# sbb-shield.net
KiCad netlist of a schematic drawn in EAGLE
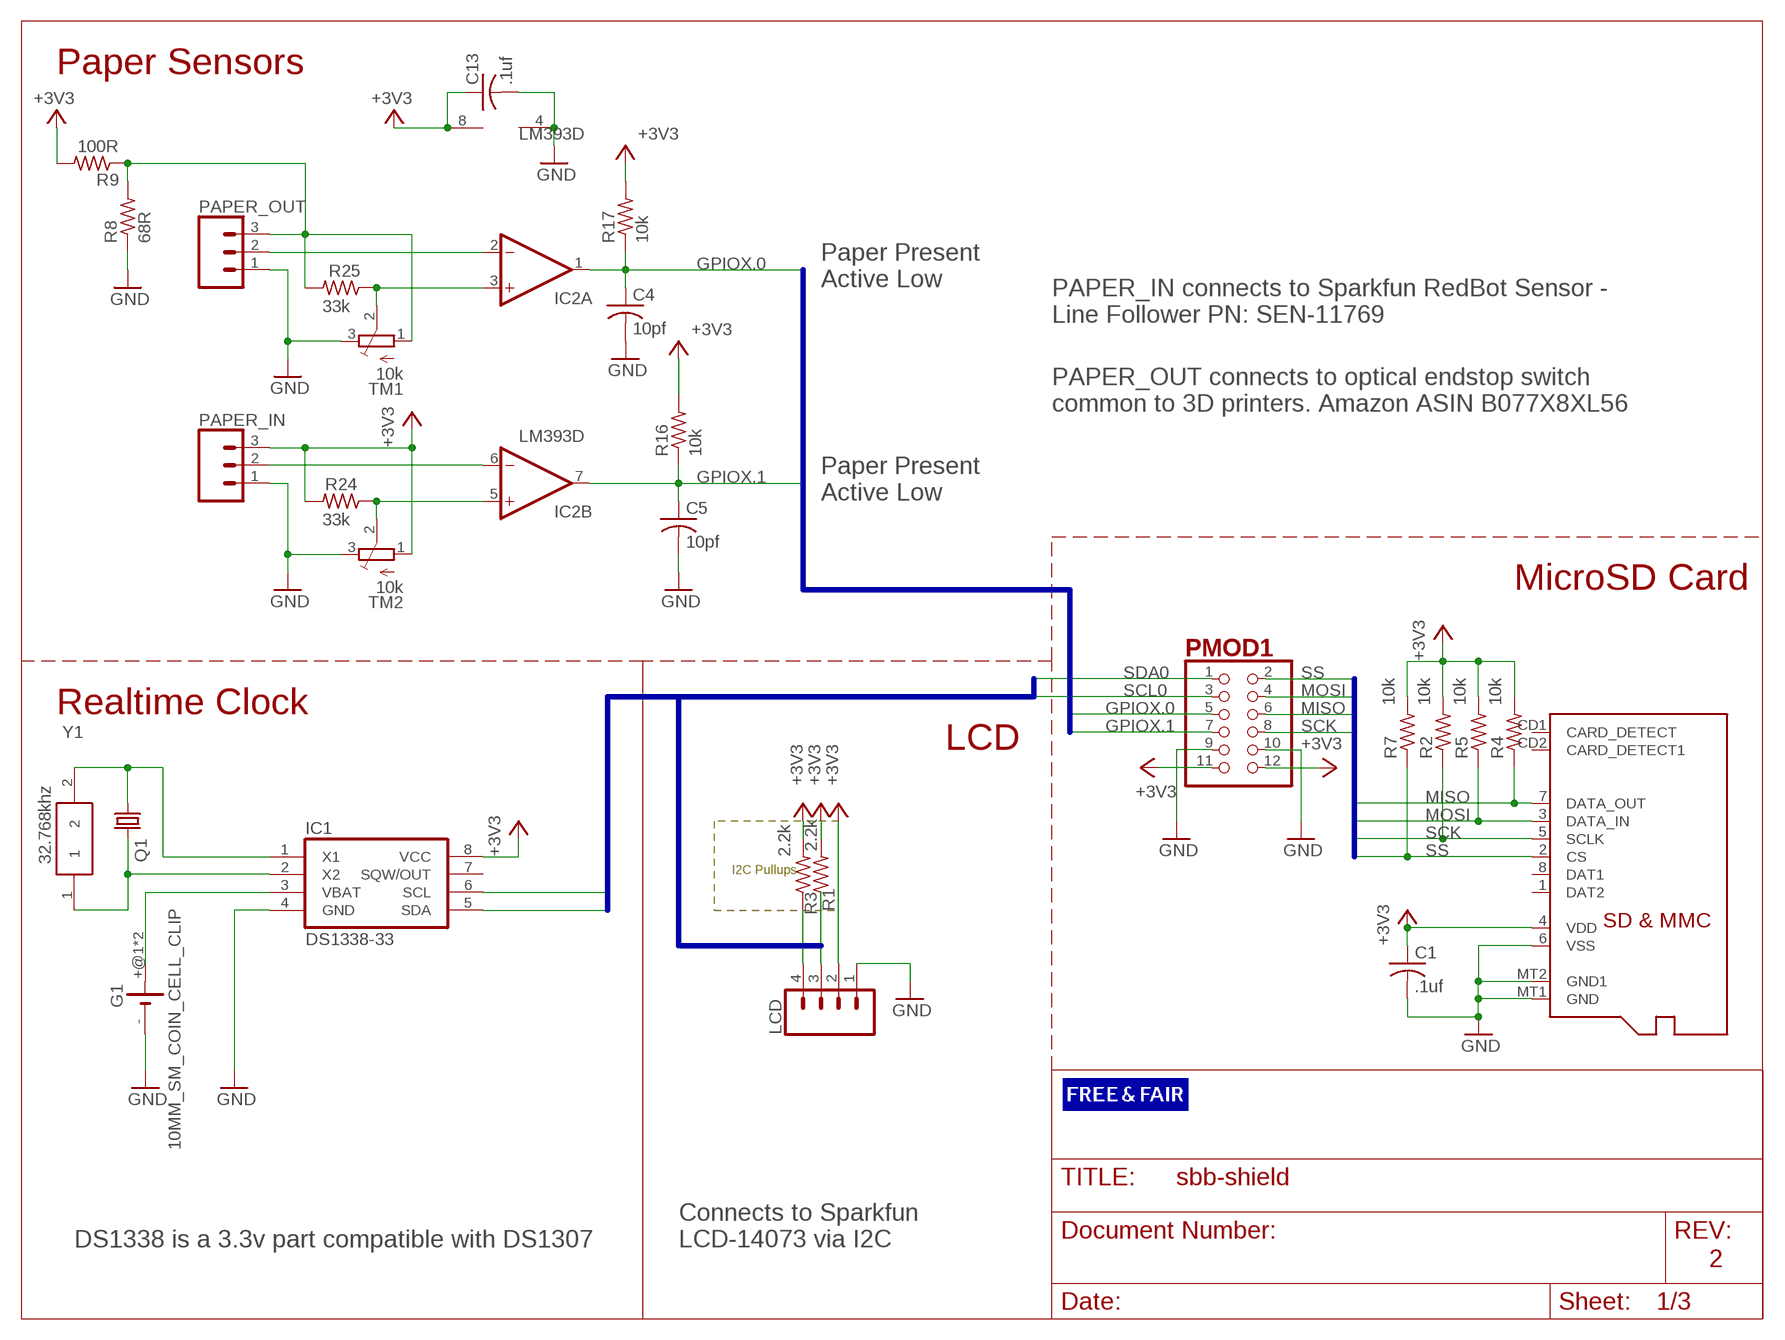
[diagram p0: schematic, sheet 1]
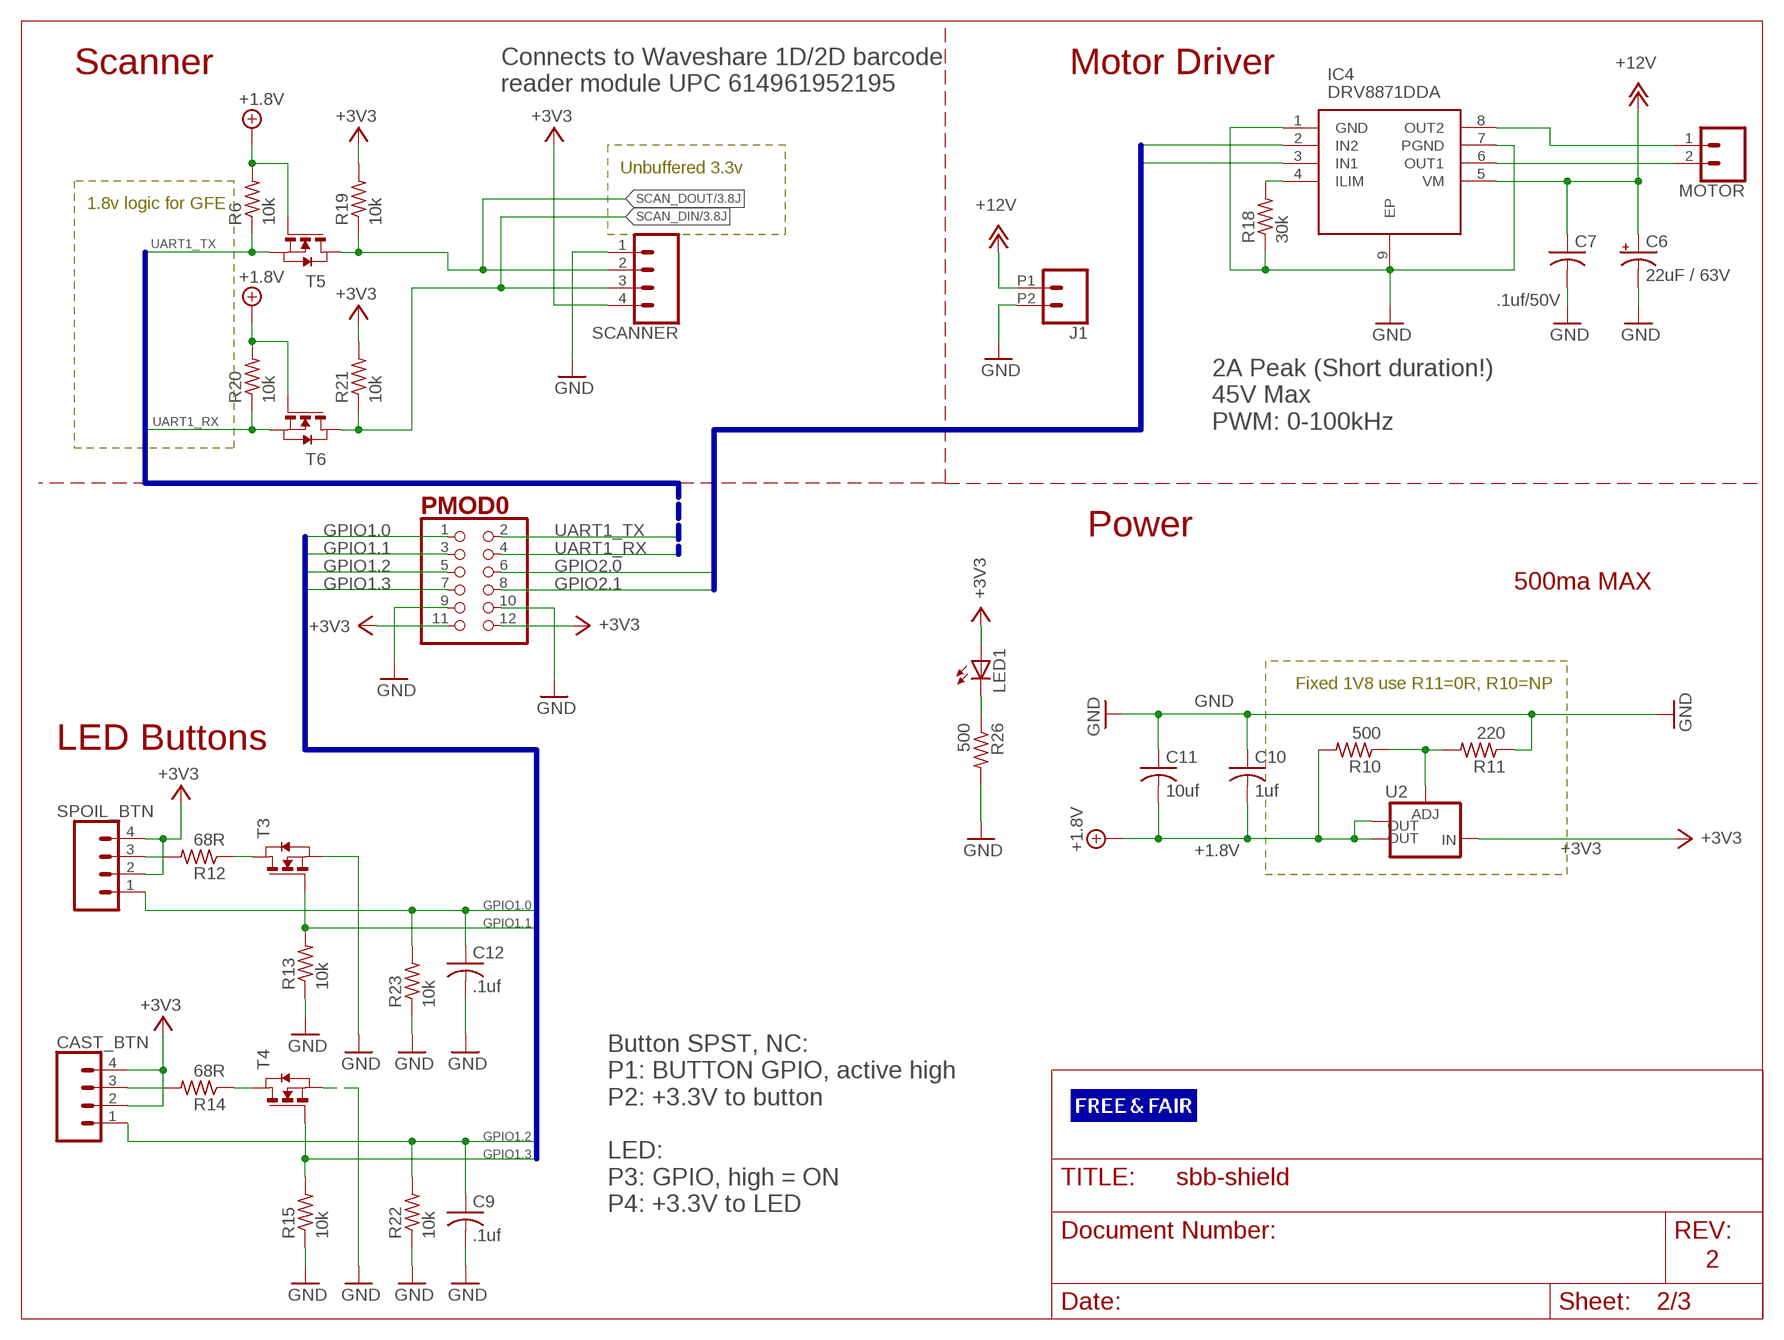
[diagram p1: schematic, sheet 2]
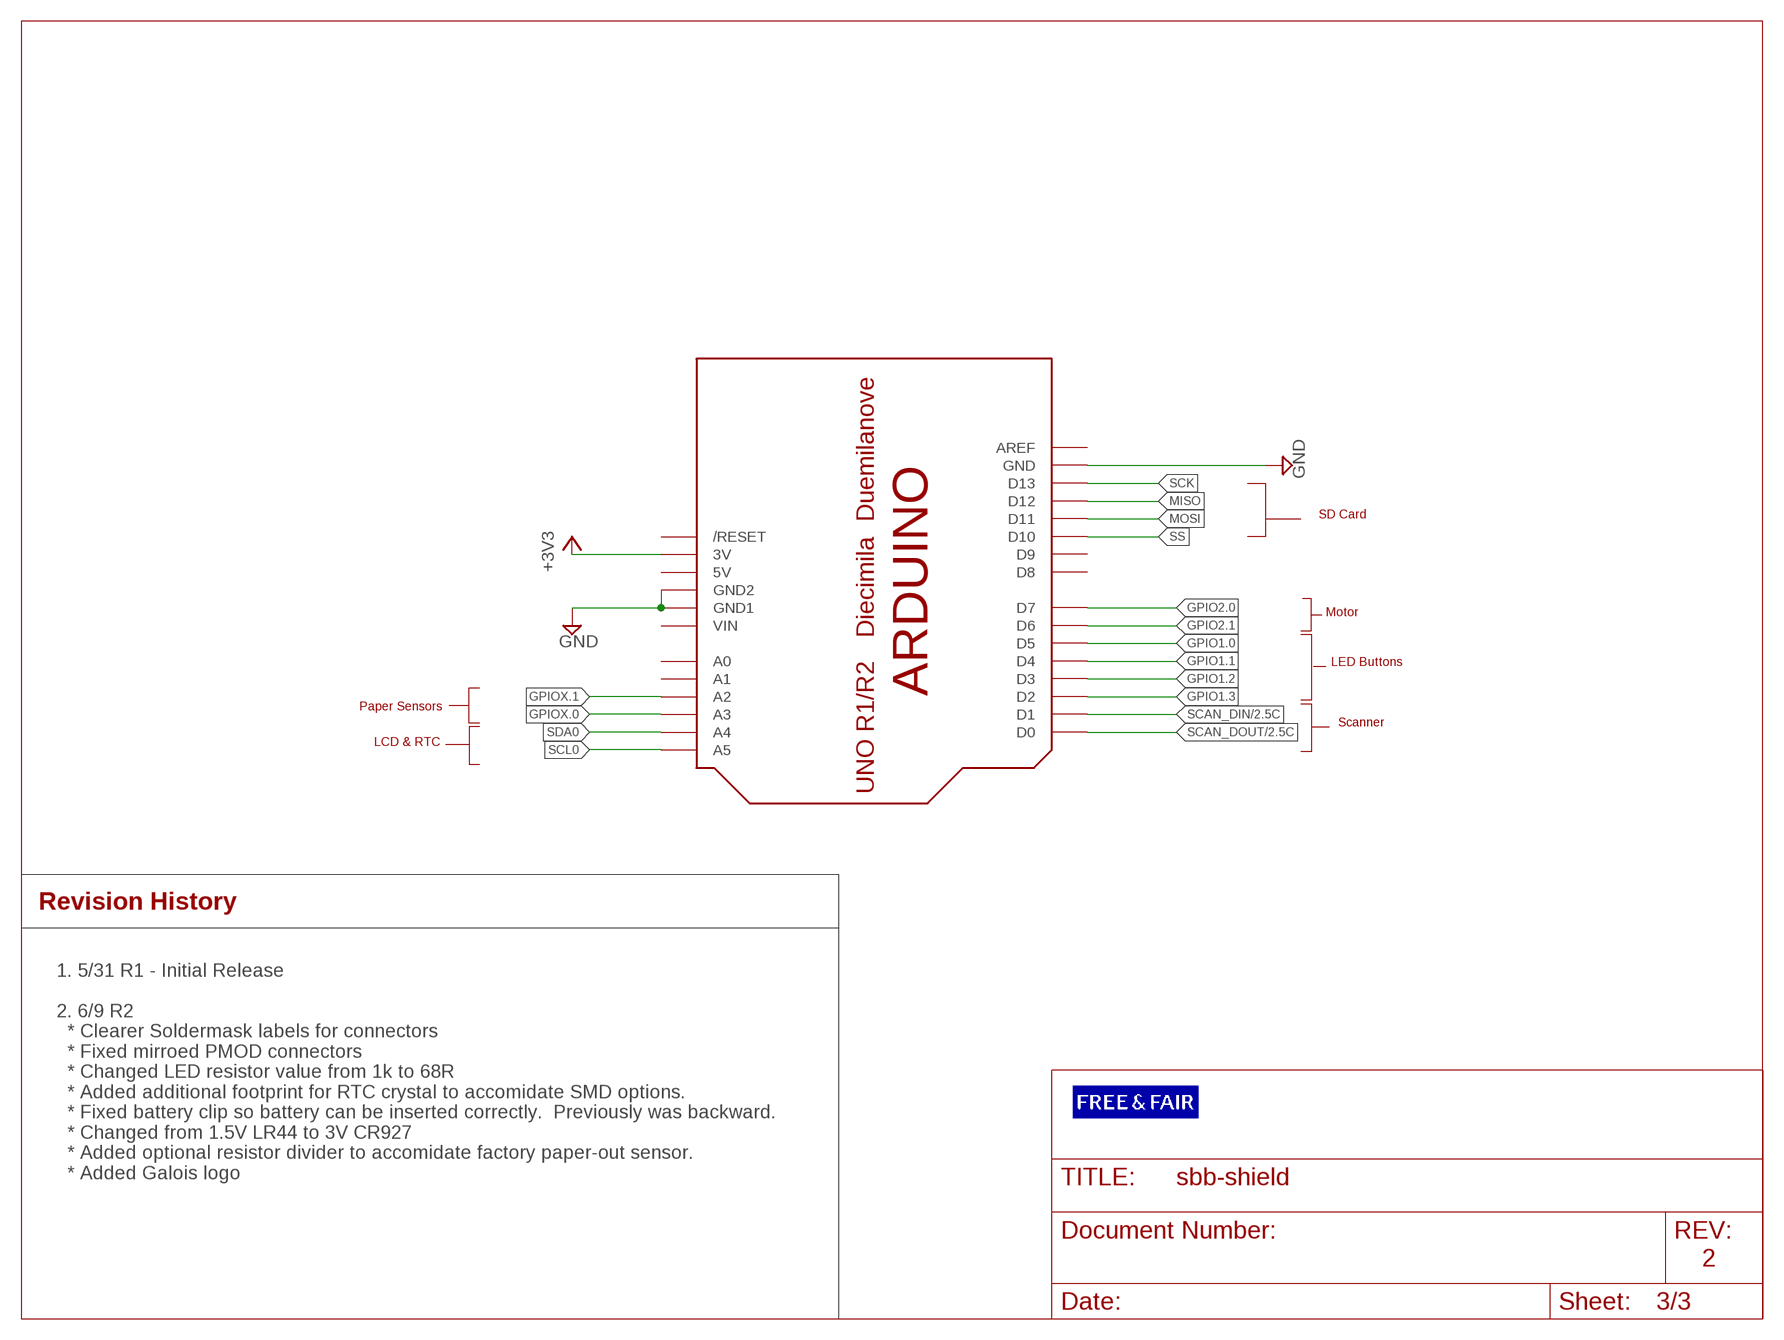
[diagram p2: schematic, sheet 3]

(export (version "E")
  (design (tool "Eeschema 10.0.6"))
  (components
    (comp (ref "U$2")
      (value "ARDUINO-NOHOLE")
      (footprint "eagle-import:ARDUINO-NOHOLE")
      (libsource (lib "eagle-import") (part "ARDUINO-NOHOLE"))
    )
    (comp (ref "C6")
      (value "22uF / 63V")
      (footprint "eagle-import:PANASONIC_D")
      (libsource (lib "eagle-import") (part "CPOL-USD"))
    )
    (comp (ref "C7")
      (value ".1uf/50V")
      (footprint "eagle-import:C0805K")
      (libsource (lib "eagle-import") (part "C-USC0805K"))
    )
    (comp (ref "C9")
      (value ".1uf")
      (footprint "eagle-import:C0603K")
      (libsource (lib "eagle-import") (part "rcl_334_C-USC0603K"))
    )
    (comp (ref "C10")
      (value "1uf")
      (footprint "eagle-import:C0603K")
      (libsource (lib "eagle-import") (part "rcl_334_C-USC0603K"))
    )
    (comp (ref "C11")
      (value "10uf")
      (footprint "eagle-import:C1206K")
      (libsource (lib "eagle-import") (part "resistor_348_C-USC1206K"))
    )
    (comp (ref "C12")
      (value ".1uf")
      (footprint "eagle-import:C0603K")
      (libsource (lib "eagle-import") (part "rcl_334_C-USC0603K"))
    )
    (comp (ref "CAST_BTN")
      (value "CONN_04POLAR_LOCK")
      (footprint "eagle-import:MOLEX-1X4_LOCK")
      (libsource (lib "eagle-import") (part "CONN_04POLAR_LOCK"))
    )
    (comp (ref "IC4")
      (value "DRV8871DDA")
      (footprint "eagle-import:SOIC127P600X170-9N")
      (fields (field (name "MOUSER_PART_NUMBER") "595-DRV8871DDA"))
      (libsource (lib "eagle-import") (part "DRV8871DDA"))
    )
    (comp (ref "J1")
      (value "CONN_022.54MM_SCREWTERM")
      (footprint "eagle-import:1X02_2.54_SCREWTERM")
      (libsource (lib "eagle-import") (part "CONN_022.54MM_SCREWTERM"))
    )
    (comp (ref "LED1")
      (value "LEDCHIP-LED0603")
      (footprint "eagle-import:CHIP-LED0603")
      (libsource (lib "eagle-import") (part "LEDCHIP-LED0603"))
    )
    (comp (ref "MOTOR")
      (value "CONN_02POLAR_LOCK")
      (footprint "eagle-import:MOLEX-1X2_LOCK")
      (libsource (lib "eagle-import") (part "CONN_02POLAR_LOCK"))
    )
    (comp (ref "PMOD0")
      (value "PINHD-2X6")
      (footprint "eagle-import:2X06")
      (libsource (lib "eagle-import") (part "PINHD-2X6"))
    )
    (comp (ref "R6")
      (value "10k")
      (footprint "eagle-import:R0603")
      (libsource (lib "eagle-import") (part "R-US_R0603"))
    )
    (comp (ref "R10")
      (value "500")
      (footprint "eagle-import:R0603")
      (libsource (lib "eagle-import") (part "resistor_348_R-US_R0603"))
    )
    (comp (ref "R11")
      (value "220")
      (footprint "eagle-import:R0603")
      (libsource (lib "eagle-import") (part "resistor_348_R-US_R0603"))
    )
    (comp (ref "R12")
      (value "68R")
      (footprint "eagle-import:R0603")
      (libsource (lib "eagle-import") (part "R-US_R0603"))
    )
    (comp (ref "R13")
      (value "10k")
      (footprint "eagle-import:R0603")
      (libsource (lib "eagle-import") (part "R-US_R0603"))
    )
    (comp (ref "R14")
      (value "68R")
      (footprint "eagle-import:R0603")
      (libsource (lib "eagle-import") (part "R-US_R0603"))
    )
    (comp (ref "R15")
      (value "10k")
      (footprint "eagle-import:R0603")
      (libsource (lib "eagle-import") (part "R-US_R0603"))
    )
    (comp (ref "R18")
      (value "30k")
      (footprint "eagle-import:R0603")
      (libsource (lib "eagle-import") (part "R-US_R0603"))
    )
    (comp (ref "R19")
      (value "10k")
      (footprint "eagle-import:R0603")
      (libsource (lib "eagle-import") (part "R-US_R0603"))
    )
    (comp (ref "R20")
      (value "10k")
      (footprint "eagle-import:R0603")
      (libsource (lib "eagle-import") (part "R-US_R0603"))
    )
    (comp (ref "R21")
      (value "10k")
      (footprint "eagle-import:R0603")
      (libsource (lib "eagle-import") (part "R-US_R0603"))
    )
    (comp (ref "R22")
      (value "10k")
      (footprint "eagle-import:R0603")
      (libsource (lib "eagle-import") (part "R-US_R0603"))
    )
    (comp (ref "R23")
      (value "10k")
      (footprint "eagle-import:R0603")
      (libsource (lib "eagle-import") (part "R-US_R0603"))
    )
    (comp (ref "R26")
      (value "500")
      (footprint "eagle-import:R0603")
      (libsource (lib "eagle-import") (part "resistor_348_R-US_R0603"))
    )
    (comp (ref "SCANNER")
      (value "CONN_04POLAR_LOCK")
      (footprint "eagle-import:MOLEX-1X4_LOCK")
      (libsource (lib "eagle-import") (part "CONN_04POLAR_LOCK"))
    )
    (comp (ref "SPOIL_BTN")
      (value "CONN_04POLAR_LOCK")
      (footprint "eagle-import:MOLEX-1X4_LOCK")
      (libsource (lib "eagle-import") (part "CONN_04POLAR_LOCK"))
    )
    (comp (ref "T3")
      (value "PMV65UNEAR")
      (footprint "eagle-import:SOT-23")
      (libsource (lib "eagle-import") (part "NMOSSOT23"))
    )
    (comp (ref "T4")
      (value "PMV65UNEAR")
      (footprint "eagle-import:SOT-23")
      (libsource (lib "eagle-import") (part "NMOSSOT23"))
    )
    (comp (ref "T5")
      (value "PMV65UNEAR")
      (footprint "eagle-import:SOT-23")
      (libsource (lib "eagle-import") (part "NMOSSOT23"))
    )
    (comp (ref "T6")
      (value "PMV65UNEAR")
      (footprint "eagle-import:SOT-23")
      (libsource (lib "eagle-import") (part "NMOSSOT23"))
    )
    (comp (ref "U2")
      (value "V_REG_LM1117SOT223")
      (footprint "eagle-import:SOT223")
      (libsource (lib "eagle-import") (part "V_REG_LM1117SOT223"))
    )
    (comp (ref "C1")
      (value ".1uf")
      (footprint "eagle-import:C0603K")
      (libsource (lib "eagle-import") (part "C-USC0603K"))
    )
    (comp (ref "C4")
      (value "10pf")
      (footprint "eagle-import:C0603K")
      (libsource (lib "eagle-import") (part "C-USC0603K"))
    )
    (comp (ref "C5")
      (value "10pf")
      (footprint "eagle-import:C0603K")
      (libsource (lib "eagle-import") (part "C-USC0603K"))
    )
    (comp (ref "C13")
      (value ".1uf")
      (footprint "eagle-import:C0603K")
      (libsource (lib "eagle-import") (part "C-USC0603K"))
    )
    (comp (ref "G1")
      (value "10MM_SM_COIN_CELL_CLIP")
      (footprint "eagle-import:10MM_SM_COIN_CELL_CLIP")
      (libsource (lib "eagle-import") (part "10MM_SM_COIN_CELL_CLIP"))
    )
    (comp (ref "IC1")
      (value "DS1338-33")
      (footprint "eagle-import:SO-8")
      (libsource (lib "eagle-import") (part "IC_RTC_DS1307"))
    )
    (comp (ref "IC2")
      (value "LM393D")
      (footprint "eagle-import:SO08")
      (libsource (lib "eagle-import") (part "LM393D"))
    )
    (comp (ref "LCD")
      (value "CONN_04POLAR_LOCK")
      (footprint "eagle-import:MOLEX-1X4_LOCK")
      (libsource (lib "eagle-import") (part "CONN_04POLAR_LOCK"))
    )
    (comp (ref "PAPER_IN")
      (value "CONN_03POLAR_LOCK")
      (footprint "eagle-import:MOLEX-1X3_LOCK")
      (libsource (lib "eagle-import") (part "CONN_03POLAR_LOCK"))
    )
    (comp (ref "PAPER_OUT")
      (value "CONN_03POLAR_LOCK")
      (footprint "eagle-import:MOLEX-1X3_LOCK")
      (libsource (lib "eagle-import") (part "CONN_03POLAR_LOCK"))
    )
    (comp (ref "PMOD1")
      (value "PINHD-2X6")
      (footprint "eagle-import:2X06")
      (libsource (lib "eagle-import") (part "PINHD-2X6"))
    )
    (comp (ref "Q1")
      (value "32.768khz")
      (footprint "eagle-import:TC26H")
      (libsource (lib "eagle-import") (part "CRYSTALTC26H"))
    )
    (comp (ref "R1")
      (value "2.2k")
      (footprint "eagle-import:R0603")
      (libsource (lib "eagle-import") (part "R-US_R0603"))
    )
    (comp (ref "R2")
      (value "10k")
      (footprint "eagle-import:R0603")
      (libsource (lib "eagle-import") (part "R-US_R0603"))
    )
    (comp (ref "R3")
      (value "2.2k")
      (footprint "eagle-import:R0603")
      (libsource (lib "eagle-import") (part "R-US_R0603"))
    )
    (comp (ref "R4")
      (value "10k")
      (footprint "eagle-import:R0603")
      (libsource (lib "eagle-import") (part "R-US_R0603"))
    )
    (comp (ref "R5")
      (value "10k")
      (footprint "eagle-import:R0603")
      (libsource (lib "eagle-import") (part "R-US_R0603"))
    )
    (comp (ref "R7")
      (value "10k")
      (footprint "eagle-import:R0603")
      (libsource (lib "eagle-import") (part "R-US_R0603"))
    )
    (comp (ref "R8")
      (value "68R")
      (footprint "eagle-import:R0603")
      (libsource (lib "eagle-import") (part "R-US_R0603"))
    )
    (comp (ref "R9")
      (value "100R")
      (footprint "eagle-import:R0603")
      (libsource (lib "eagle-import") (part "R-US_R0603"))
    )
    (comp (ref "R16")
      (value "10k")
      (footprint "eagle-import:R0603")
      (libsource (lib "eagle-import") (part "R-US_R0603"))
    )
    (comp (ref "R17")
      (value "10k")
      (footprint "eagle-import:R0603")
      (libsource (lib "eagle-import") (part "R-US_R0603"))
    )
    (comp (ref "R24")
      (value "33k")
      (footprint "eagle-import:R0603")
      (libsource (lib "eagle-import") (part "R-US_R0603"))
    )
    (comp (ref "R25")
      (value "33k")
      (footprint "eagle-import:R0603")
      (libsource (lib "eagle-import") (part "R-US_R0603"))
    )
    (comp (ref "TM1")
      (value "10k")
      (footprint "eagle-import:TC33X")
      (libsource (lib "eagle-import") (part "TRIMPOTTC33X"))
    )
    (comp (ref "TM2")
      (value "10k")
      (footprint "eagle-import:TC33X")
      (libsource (lib "eagle-import") (part "TRIMPOTTC33X"))
    )
    (comp (ref "U1")
      (value "MICROSD")
      (footprint "eagle-import:MICROSD")
      (libsource (lib "eagle-import") (part "MICROSD"))
    )
    (comp (ref "Y1")
      (value "32.768khz")
      (footprint "eagle-import:ABS07AIG32768KHZ71T")
      (fields
        (field (name "MANUFACTURER_PART_NUMBER") "ABS07W-32.768kHz-D-1-T")
        (field (name "MOUSER_PART_NUMBER") "815-ABS07W32.768KD1T")
      )
      (libsource (lib "eagle-import") (part "ABS07W-32.768KHZ-D-1-T"))
    )
  )
  (nets
    (net (code "1") (name "+1.8V") (class "Default")
      (node (ref "C10") (pin "2") (pinfunction "2_2") (pintype "passive"))
      (node (ref "C11") (pin "2") (pinfunction "2_2") (pintype "passive"))
      (node (ref "R10") (pin "2") (pinfunction "2_2") (pintype "passive"))
      (node (ref "R20") (pin "2") (pinfunction "2_2") (pintype "passive"))
      (node (ref "R6") (pin "2") (pinfunction "2_2") (pintype "passive"))
      (node (ref "T5") (pin "3") (pinfunction "G_3") (pintype "passive"))
      (node (ref "T6") (pin "3") (pinfunction "G_3") (pintype "passive"))
      (node (ref "U2") (pin "2") (pinfunction "OUT_2") (pintype "output"))
      (node (ref "U2") (pin "4") (pinfunction "OUT_4") (pintype "output"))
    )
    (net (code "2") (name "+3V3") (class "Default")
      (node (ref "C1") (pin "1") (pinfunction "1_1") (pintype "passive"))
      (node (ref "C13") (pin "1") (pinfunction "1_1") (pintype "passive"))
      (node (ref "CAST_BTN") (pin "2") (pinfunction "2_2") (pintype "passive"))
      (node (ref "CAST_BTN") (pin "4") (pinfunction "4_4") (pintype "passive"))
      (node (ref "IC1") (pin "8") (pinfunction "VCC_8") (pintype "bidirectional"))
      (node (ref "IC2") (pin "8") (pinfunction "V+_8") (pintype "power_in"))
      (node (ref "LCD") (pin "2") (pinfunction "2_2") (pintype "passive"))
      (node (ref "LED1") (pin "A") (pinfunction "A_A") (pintype "passive"))
      (node (ref "PAPER_IN") (pin "3") (pinfunction "3_3") (pintype "passive"))
      (node (ref "PMOD0") (pin "11") (pinfunction "11_11") (pintype "passive"))
      (node (ref "PMOD0") (pin "12") (pinfunction "12_12") (pintype "passive"))
      (node (ref "PMOD1") (pin "11") (pinfunction "11_11") (pintype "passive"))
      (node (ref "PMOD1") (pin "12") (pinfunction "12_12") (pintype "passive"))
      (node (ref "R1") (pin "2") (pinfunction "2_2") (pintype "passive"))
      (node (ref "R16") (pin "2") (pinfunction "2_2") (pintype "passive"))
      (node (ref "R17") (pin "2") (pinfunction "2_2") (pintype "passive"))
      (node (ref "R19") (pin "2") (pinfunction "2_2") (pintype "passive"))
      (node (ref "R2") (pin "2") (pinfunction "2_2") (pintype "passive"))
      (node (ref "R21") (pin "2") (pinfunction "2_2") (pintype "passive"))
      (node (ref "R24") (pin "2") (pinfunction "2_2") (pintype "passive"))
      (node (ref "R3") (pin "2") (pinfunction "2_2") (pintype "passive"))
      (node (ref "R4") (pin "2") (pinfunction "2_2") (pintype "passive"))
      (node (ref "R5") (pin "2") (pinfunction "2_2") (pintype "passive"))
      (node (ref "R7") (pin "2") (pinfunction "2_2") (pintype "passive"))
      (node (ref "R9") (pin "2") (pinfunction "2_2") (pintype "passive"))
      (node (ref "SCANNER") (pin "4") (pinfunction "4_4") (pintype "passive"))
      (node (ref "SPOIL_BTN") (pin "2") (pinfunction "2_2") (pintype "passive"))
      (node (ref "SPOIL_BTN") (pin "4") (pinfunction "4_4") (pintype "passive"))
      (node (ref "TM2") (pin "1") (pinfunction "A_1") (pintype "passive"))
      (node (ref "U$2") (pin "3V") (pinfunction "3V_3V") (pintype "power_in"))
      (node (ref "U1") (pin "4") (pinfunction "VDD_4") (pintype "power_in"))
      (node (ref "U2") (pin "3") (pinfunction "IN_3") (pintype "input"))
    )
    (net (code "3") (name "+12V") (class "Default")
      (node (ref "C6") (pin "+") (pinfunction "+_+") (pintype "passive"))
      (node (ref "C7") (pin "1") (pinfunction "1_1") (pintype "passive"))
      (node (ref "IC4") (pin "5") (pinfunction "VM_5") (pintype "power_in"))
      (node (ref "J1") (pin "P1") (pinfunction "1_P1") (pintype "passive"))
    )
    (net (code "4") (name "5V") (class "Default")
      (node (ref "U$2") (pin "5V") (pinfunction "5V_5V") (pintype "power_in"))
    )
    (net (code "5") (name "GND") (class "Default")
      (node (ref "C1") (pin "2") (pinfunction "2_2") (pintype "passive"))
      (node (ref "C10") (pin "1") (pinfunction "1_1") (pintype "passive"))
      (node (ref "C11") (pin "1") (pinfunction "1_1") (pintype "passive"))
      (node (ref "C12") (pin "2") (pinfunction "2_2") (pintype "passive"))
      (node (ref "C13") (pin "2") (pinfunction "2_2") (pintype "passive"))
      (node (ref "C4") (pin "2") (pinfunction "2_2") (pintype "passive"))
      (node (ref "C5") (pin "2") (pinfunction "2_2") (pintype "passive"))
      (node (ref "C6") (pin "-") (pinfunction "-_-") (pintype "passive"))
      (node (ref "C7") (pin "2") (pinfunction "2_2") (pintype "passive"))
      (node (ref "C9") (pin "2") (pinfunction "2_2") (pintype "passive"))
      (node (ref "G1") (pin "-") (pinfunction "-_-") (pintype "passive"))
      (node (ref "IC1") (pin "4") (pinfunction "GND_4") (pintype "bidirectional"))
      (node (ref "IC2") (pin "4") (pinfunction "V-_4") (pintype "power_in"))
      (node (ref "IC4") (pin "1") (pinfunction "GND_1") (pintype "power_in"))
      (node (ref "IC4") (pin "7") (pinfunction "PGND_7") (pintype "power_in"))
      (node (ref "IC4") (pin "9") (pinfunction "EP_9") (pintype "bidirectional"))
      (node (ref "J1") (pin "P2") (pinfunction "2_P2") (pintype "passive"))
      (node (ref "LCD") (pin "1") (pinfunction "1_1") (pintype "passive"))
      (node (ref "PAPER_IN") (pin "1") (pinfunction "1_1") (pintype "passive"))
      (node (ref "PAPER_OUT") (pin "1") (pinfunction "1_1") (pintype "passive"))
      (node (ref "PMOD0") (pin "10") (pinfunction "10_10") (pintype "passive"))
      (node (ref "PMOD0") (pin "9") (pinfunction "9_9") (pintype "passive"))
      (node (ref "PMOD1") (pin "10") (pinfunction "10_10") (pintype "passive"))
      (node (ref "PMOD1") (pin "9") (pinfunction "9_9") (pintype "passive"))
      (node (ref "R11") (pin "1") (pinfunction "1_1") (pintype "passive"))
      (node (ref "R13") (pin "1") (pinfunction "1_1") (pintype "passive"))
      (node (ref "R15") (pin "1") (pinfunction "1_1") (pintype "passive"))
      (node (ref "R18") (pin "1") (pinfunction "1_1") (pintype "passive"))
      (node (ref "R22") (pin "1") (pinfunction "1_1") (pintype "passive"))
      (node (ref "R23") (pin "1") (pinfunction "1_1") (pintype "passive"))
      (node (ref "R26") (pin "2") (pinfunction "2_2") (pintype "passive"))
      (node (ref "R8") (pin "1") (pinfunction "1_1") (pintype "passive"))
      (node (ref "SCANNER") (pin "1") (pinfunction "1_1") (pintype "passive"))
      (node (ref "T3") (pin "2") (pinfunction "S_2") (pintype "passive"))
      (node (ref "T4") (pin "2") (pinfunction "S_2") (pintype "passive"))
      (node (ref "TM1") (pin "3") (pinfunction "E_3") (pintype "passive"))
      (node (ref "TM2") (pin "3") (pinfunction "E_3") (pintype "passive"))
      (node (ref "U$2") (pin "GND") (pinfunction "GND_GND") (pintype "power_in"))
      (node (ref "U$2") (pin "GND1") (pinfunction "GND1_GND1") (pintype "power_in"))
      (node (ref "U$2") (pin "GND2") (pinfunction "GND2_GND2") (pintype "power_in"))
      (node (ref "U1") (pin "6") (pinfunction "VSS_6") (pintype "power_in"))
      (node (ref "U1") (pin "MT1") (pinfunction "GND_MT1") (pintype "power_in"))
      (node (ref "U1") (pin "MT2") (pinfunction "GND1_MT2") (pintype "power_in"))
    )
    (net (code "6") (name "GPIO1.0") (class "Default")
      (node (ref "C12") (pin "1") (pinfunction "1_1") (pintype "passive"))
      (node (ref "PMOD0") (pin "1") (pinfunction "1_1") (pintype "passive"))
      (node (ref "R23") (pin "2") (pinfunction "2_2") (pintype "passive"))
      (node (ref "SPOIL_BTN") (pin "1") (pinfunction "1_1") (pintype "passive"))
      (node (ref "U$2") (pin "D5") (pinfunction "D5_D5") (pintype "bidirectional"))
    )
    (net (code "7") (name "GPIO1.1") (class "Default")
      (node (ref "PMOD0") (pin "3") (pinfunction "3_3") (pintype "passive"))
      (node (ref "R13") (pin "2") (pinfunction "2_2") (pintype "passive"))
      (node (ref "T3") (pin "3") (pinfunction "G_3") (pintype "passive"))
      (node (ref "U$2") (pin "D4") (pinfunction "D4_D4") (pintype "bidirectional"))
    )
    (net (code "8") (name "GPIO1.2") (class "Default")
      (node (ref "C9") (pin "1") (pinfunction "1_1") (pintype "passive"))
      (node (ref "CAST_BTN") (pin "1") (pinfunction "1_1") (pintype "passive"))
      (node (ref "PMOD0") (pin "5") (pinfunction "5_5") (pintype "passive"))
      (node (ref "R22") (pin "2") (pinfunction "2_2") (pintype "passive"))
      (node (ref "U$2") (pin "D3") (pinfunction "D3_D3") (pintype "bidirectional"))
    )
    (net (code "9") (name "GPIO1.3") (class "Default")
      (node (ref "PMOD0") (pin "7") (pinfunction "7_7") (pintype "passive"))
      (node (ref "R15") (pin "2") (pinfunction "2_2") (pintype "passive"))
      (node (ref "T4") (pin "3") (pinfunction "G_3") (pintype "passive"))
      (node (ref "U$2") (pin "D2") (pinfunction "D2_D2") (pintype "bidirectional"))
    )
    (net (code "10") (name "GPIO2.0") (class "Default")
      (node (ref "IC4") (pin "2") (pinfunction "IN2_2") (pintype "input"))
      (node (ref "PMOD0") (pin "6") (pinfunction "6_6") (pintype "passive"))
      (node (ref "U$2") (pin "D7") (pinfunction "D7_D7") (pintype "bidirectional"))
    )
    (net (code "11") (name "GPIO2.1") (class "Default")
      (node (ref "IC4") (pin "3") (pinfunction "IN1_3") (pintype "input"))
      (node (ref "PMOD0") (pin "8") (pinfunction "8_8") (pintype "passive"))
      (node (ref "U$2") (pin "D6") (pinfunction "D6_D6") (pintype "bidirectional"))
    )
    (net (code "12") (name "GPIOX.0") (class "Default")
      (node (ref "C4") (pin "1") (pinfunction "1_1") (pintype "passive"))
      (node (ref "IC2") (pin "1") (pinfunction "OUT_1") (pintype "output"))
      (node (ref "PMOD1") (pin "5") (pinfunction "5_5") (pintype "passive"))
      (node (ref "R17") (pin "1") (pinfunction "1_1") (pintype "passive"))
      (node (ref "U$2") (pin "A3") (pinfunction "A3_A3") (pintype "bidirectional"))
    )
    (net (code "13") (name "GPIOX.1") (class "Default")
      (node (ref "C5") (pin "1") (pinfunction "1_1") (pintype "passive"))
      (node (ref "IC2") (pin "7") (pinfunction "OUT_7") (pintype "output"))
      (node (ref "PMOD1") (pin "7") (pinfunction "7_7") (pintype "passive"))
      (node (ref "R16") (pin "1") (pinfunction "1_1") (pintype "passive"))
      (node (ref "U$2") (pin "A2") (pinfunction "A2_A2") (pintype "bidirectional"))
    )
    (net (code "14") (name "MISO") (class "Default")
      (node (ref "PMOD1") (pin "6") (pinfunction "6_6") (pintype "passive"))
      (node (ref "R4") (pin "1") (pinfunction "1_1") (pintype "passive"))
      (node (ref "U$2") (pin "D12") (pinfunction "D12_D12") (pintype "bidirectional"))
      (node (ref "U1") (pin "7") (pinfunction "DATA_OUT_7") (pintype "output"))
    )
    (net (code "15") (name "MOSI") (class "Default")
      (node (ref "PMOD1") (pin "4") (pinfunction "4_4") (pintype "passive"))
      (node (ref "R5") (pin "1") (pinfunction "1_1") (pintype "passive"))
      (node (ref "U$2") (pin "D11") (pinfunction "D11_D11") (pintype "bidirectional"))
      (node (ref "U1") (pin "3") (pinfunction "DATA_IN_3") (pintype "input"))
    )
    (net (code "16") (name "Net-(CAST_BTN-Pad3)") (class "Default")
      (node (ref "CAST_BTN") (pin "3") (pinfunction "3_3") (pintype "passive"))
      (node (ref "R14") (pin "2") (pinfunction "2_2") (pintype "passive"))
    )
    (net (code "17") (name "Net-(IC1-VBAT)") (class "Default")
      (node (ref "G1") (pin "+@1") (pinfunction "+_+@1") (pintype "passive"))
      (node (ref "G1") (pin "+@2") (pinfunction "+_+@2") (pintype "passive"))
      (node (ref "IC1") (pin "3") (pinfunction "VBAT_3") (pintype "bidirectional"))
    )
    (net (code "18") (name "Net-(IC1-X1)") (class "Default")
      (node (ref "IC1") (pin "1") (pinfunction "X1_1") (pintype "bidirectional"))
      (node (ref "Q1") (pin "1") (pinfunction "1_1") (pintype "passive"))
      (node (ref "Y1") (pin "2") (pinfunction "2_2") (pintype "bidirectional"))
    )
    (net (code "19") (name "Net-(IC1-X2)") (class "Default")
      (node (ref "IC1") (pin "2") (pinfunction "X2_2") (pintype "bidirectional"))
      (node (ref "Q1") (pin "2") (pinfunction "2_2") (pintype "passive"))
      (node (ref "Y1") (pin "1") (pinfunction "1_1") (pintype "bidirectional"))
    )
    (net (code "20") (name "Net-(IC2A-+IN)") (class "Default")
      (node (ref "IC2") (pin "3") (pinfunction "+IN_3") (pintype "input"))
      (node (ref "R25") (pin "1") (pinfunction "1_1") (pintype "passive"))
      (node (ref "TM1") (pin "2") (pinfunction "S_2") (pintype "passive"))
    )
    (net (code "21") (name "Net-(IC2A--IN)") (class "Default")
      (node (ref "IC2") (pin "2") (pinfunction "-IN_2") (pintype "input"))
      (node (ref "PAPER_OUT") (pin "2") (pinfunction "2_2") (pintype "passive"))
    )
    (net (code "22") (name "Net-(IC2B-+IN)") (class "Default")
      (node (ref "IC2") (pin "5") (pinfunction "+IN_5") (pintype "input"))
      (node (ref "R24") (pin "1") (pinfunction "1_1") (pintype "passive"))
      (node (ref "TM2") (pin "2") (pinfunction "S_2") (pintype "passive"))
    )
    (net (code "23") (name "Net-(IC2B--IN)") (class "Default")
      (node (ref "IC2") (pin "6") (pinfunction "-IN_6") (pintype "input"))
      (node (ref "PAPER_IN") (pin "2") (pinfunction "2_2") (pintype "passive"))
    )
    (net (code "24") (name "Net-(IC4-ILIM)") (class "Default")
      (node (ref "IC4") (pin "4") (pinfunction "ILIM_4") (pintype "input"))
      (node (ref "R18") (pin "2") (pinfunction "2_2") (pintype "passive"))
    )
    (net (code "25") (name "Net-(IC4-OUT1)") (class "Default")
      (node (ref "IC4") (pin "6") (pinfunction "OUT1_6") (pintype "output"))
      (node (ref "MOTOR") (pin "2") (pinfunction "2_2") (pintype "passive"))
    )
    (net (code "26") (name "Net-(IC4-OUT2)") (class "Default")
      (node (ref "IC4") (pin "8") (pinfunction "OUT2_8") (pintype "output"))
      (node (ref "MOTOR") (pin "1") (pinfunction "1_1") (pintype "passive"))
    )
    (net (code "27") (name "Net-(LED1-PadC)") (class "Default")
      (node (ref "LED1") (pin "C") (pinfunction "C_C") (pintype "passive"))
      (node (ref "R26") (pin "1") (pinfunction "1_1") (pintype "passive"))
    )
    (net (code "28") (name "Net-(R12-Pad2)") (class "Default")
      (node (ref "R12") (pin "2") (pinfunction "2_2") (pintype "passive"))
      (node (ref "SPOIL_BTN") (pin "3") (pinfunction "3_3") (pintype "passive"))
    )
    (net (code "29") (name "Net-(T3-D)") (class "Default")
      (node (ref "R12") (pin "1") (pinfunction "1_1") (pintype "passive"))
      (node (ref "T3") (pin "1") (pinfunction "D_1") (pintype "passive"))
    )
    (net (code "30") (name "Net-(T4-D)") (class "Default")
      (node (ref "R14") (pin "1") (pinfunction "1_1") (pintype "passive"))
      (node (ref "T4") (pin "1") (pinfunction "D_1") (pintype "passive"))
    )
    (net (code "31") (name "Net-(TM1-A)") (class "Default")
      (node (ref "PAPER_OUT") (pin "3") (pinfunction "3_3") (pintype "passive"))
      (node (ref "R25") (pin "2") (pinfunction "2_2") (pintype "passive"))
      (node (ref "R8") (pin "2") (pinfunction "2_2") (pintype "passive"))
      (node (ref "R9") (pin "1") (pinfunction "1_1") (pintype "passive"))
      (node (ref "TM1") (pin "1") (pinfunction "A_1") (pintype "passive"))
    )
    (net (code "32") (name "Net-(U2-ADJ)") (class "Default")
      (node (ref "R10") (pin "1") (pinfunction "1_1") (pintype "passive"))
      (node (ref "R11") (pin "2") (pinfunction "2_2") (pintype "passive"))
      (node (ref "U2") (pin "1") (pinfunction "ADJ_1") (pintype "input"))
    )
    (net (code "33") (name "SCAN_DIN") (class "Default")
      (node (ref "R21") (pin "1") (pinfunction "1_1") (pintype "passive"))
      (node (ref "SCANNER") (pin "3") (pinfunction "3_3") (pintype "passive"))
      (node (ref "T6") (pin "1") (pinfunction "D_1") (pintype "passive"))
      (node (ref "U$2") (pin "D1") (pinfunction "D1_D1") (pintype "bidirectional"))
    )
    (net (code "34") (name "SCAN_DOUT") (class "Default")
      (node (ref "R19") (pin "1") (pinfunction "1_1") (pintype "passive"))
      (node (ref "SCANNER") (pin "2") (pinfunction "2_2") (pintype "passive"))
      (node (ref "T5") (pin "1") (pinfunction "D_1") (pintype "passive"))
      (node (ref "U$2") (pin "D0") (pinfunction "D0_D0") (pintype "bidirectional"))
    )
    (net (code "35") (name "SCK") (class "Default")
      (node (ref "PMOD1") (pin "8") (pinfunction "8_8") (pintype "passive"))
      (node (ref "R2") (pin "1") (pinfunction "1_1") (pintype "passive"))
      (node (ref "U$2") (pin "D13") (pinfunction "D13_D13") (pintype "bidirectional"))
      (node (ref "U1") (pin "5") (pinfunction "SCLK_5") (pintype "input"))
    )
    (net (code "36") (name "SCL0") (class "Default")
      (node (ref "IC1") (pin "6") (pinfunction "SCL_6") (pintype "bidirectional"))
      (node (ref "LCD") (pin "4") (pinfunction "4_4") (pintype "passive"))
      (node (ref "PMOD1") (pin "3") (pinfunction "3_3") (pintype "passive"))
      (node (ref "R3") (pin "1") (pinfunction "1_1") (pintype "passive"))
      (node (ref "U$2") (pin "A5") (pinfunction "A5_A5") (pintype "bidirectional"))
    )
    (net (code "37") (name "SDA0") (class "Default")
      (node (ref "IC1") (pin "5") (pinfunction "SDA_5") (pintype "bidirectional"))
      (node (ref "LCD") (pin "3") (pinfunction "3_3") (pintype "passive"))
      (node (ref "PMOD1") (pin "1") (pinfunction "1_1") (pintype "passive"))
      (node (ref "R1") (pin "1") (pinfunction "1_1") (pintype "passive"))
      (node (ref "U$2") (pin "A4") (pinfunction "A4_A4") (pintype "bidirectional"))
    )
    (net (code "38") (name "SS") (class "Default")
      (node (ref "PMOD1") (pin "2") (pinfunction "2_2") (pintype "passive"))
      (node (ref "R7") (pin "1") (pinfunction "1_1") (pintype "passive"))
      (node (ref "U$2") (pin "D10") (pinfunction "D10_D10") (pintype "bidirectional"))
      (node (ref "U1") (pin "2") (pinfunction "CS_2") (pintype "input"))
    )
    (net (code "39") (name "UART1_RX") (class "Default")
      (node (ref "PMOD0") (pin "4") (pinfunction "4_4") (pintype "passive"))
      (node (ref "R20") (pin "1") (pinfunction "1_1") (pintype "passive"))
      (node (ref "T6") (pin "2") (pinfunction "S_2") (pintype "passive"))
    )
    (net (code "40") (name "UART1_TX") (class "Default")
      (node (ref "PMOD0") (pin "2") (pinfunction "2_2") (pintype "passive"))
      (node (ref "R6") (pin "1") (pinfunction "1_1") (pintype "passive"))
      (node (ref "T5") (pin "2") (pinfunction "S_2") (pintype "passive"))
    )
    (net (code "41") (name "VIN") (class "Default")
      (node (ref "U$2") (pin "VIN") (pinfunction "VIN_VIN") (pintype "power_in"))
    )
    (net (code "42") (name "unconnected-(IC1-SQW{slash}OUT-Pad7)") (class "Default")
      (node (ref "IC1") (pin "7") (pinfunction "SQW/OUT_7") (pintype "bidirectional"))
    )
    (net (code "43") (name "unconnected-(U$2-PadA0)") (class "Default")
      (node (ref "U$2") (pin "A0") (pinfunction "A0_A0") (pintype "bidirectional"))
    )
    (net (code "44") (name "unconnected-(U$2-PadA1)") (class "Default")
      (node (ref "U$2") (pin "A1") (pinfunction "A1_A1") (pintype "bidirectional"))
    )
    (net (code "45") (name "unconnected-(U$2-PadAREF)") (class "Default")
      (node (ref "U$2") (pin "AREF") (pinfunction "AREF_AREF") (pintype "bidirectional"))
    )
    (net (code "46") (name "unconnected-(U$2-PadD8)") (class "Default")
      (node (ref "U$2") (pin "D8") (pinfunction "D8_D8") (pintype "bidirectional"))
    )
    (net (code "47") (name "unconnected-(U$2-PadD9)") (class "Default")
      (node (ref "U$2") (pin "D9") (pinfunction "D9_D9") (pintype "bidirectional"))
    )
    (net (code "48") (name "unconnected-(U$2-{slash}RESET-PadRESET)") (class "Default")
      (node (ref "U$2") (pin "RESET") (pinfunction "/RESET_RESET") (pintype "bidirectional"))
    )
    (net (code "49") (name "unconnected-(U1-CARD_DETECT-PadCD1)") (class "Default")
      (node (ref "U1") (pin "CD1") (pinfunction "CARD_DETECT_CD1") (pintype "passive"))
    )
    (net (code "50") (name "unconnected-(U1-CARD_DETECT1-PadCD2)") (class "Default")
      (node (ref "U1") (pin "CD2") (pinfunction "CARD_DETECT1_CD2") (pintype "passive"))
    )
    (net (code "51") (name "unconnected-(U1-DAT1-Pad8)") (class "Default")
      (node (ref "U1") (pin "8") (pinfunction "DAT1_8") (pintype "bidirectional"))
    )
    (net (code "52") (name "unconnected-(U1-DAT2-Pad1)") (class "Default")
      (node (ref "U1") (pin "1") (pinfunction "DAT2_1") (pintype "bidirectional"))
    )
  )
)
